# BIT_Level_Shift.net
KiCad netlist of a schematic drawn in Altium Designer
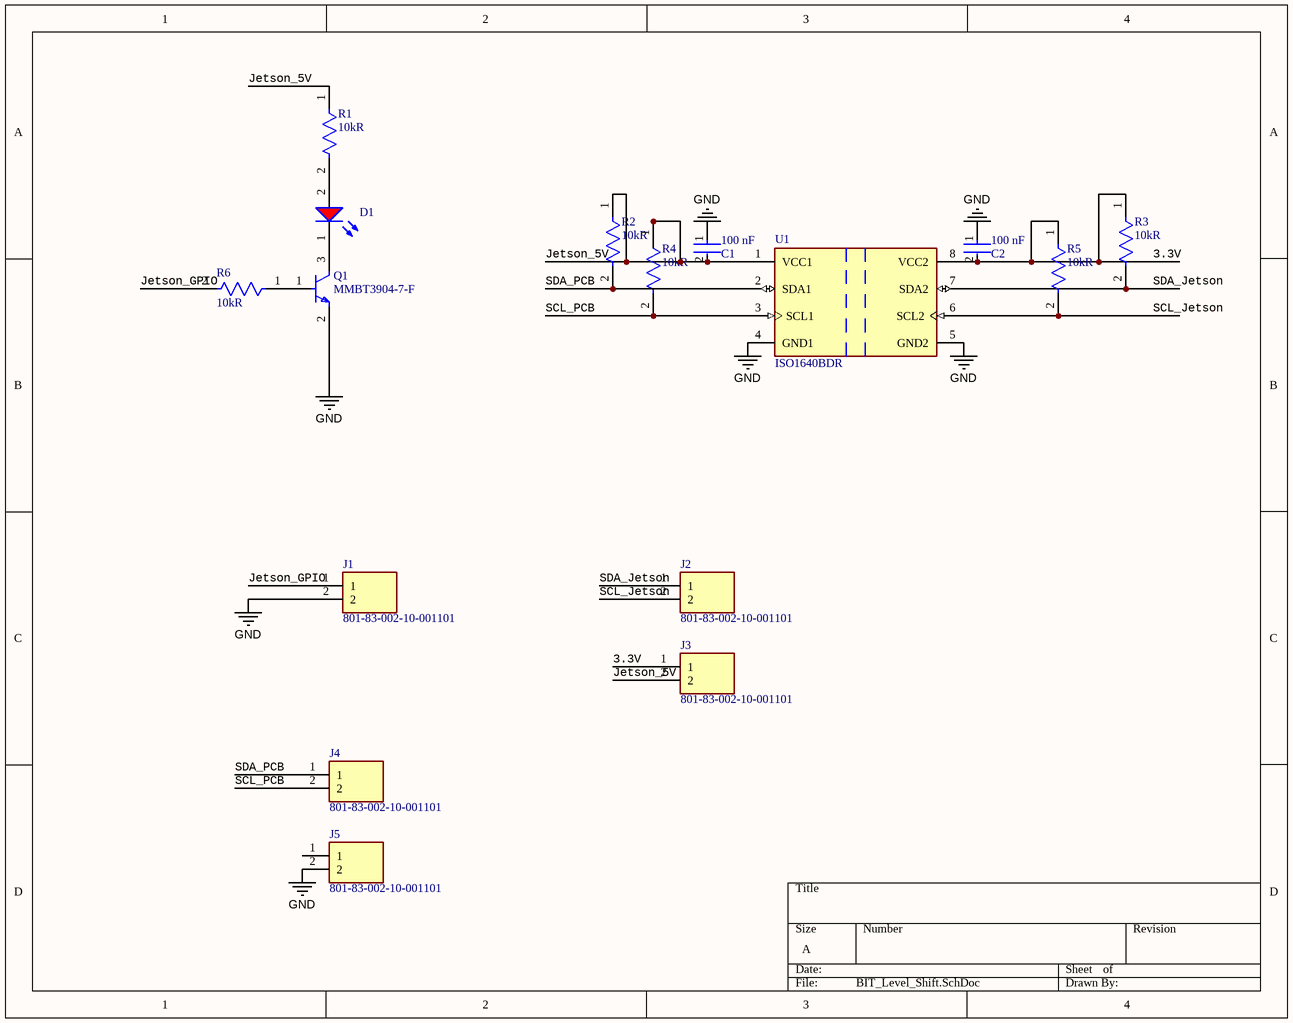
[diagram p0: BIT_Level_Shift.SchDoc]

(export (version "E")
  (design (tool "Eeschema 10.0.6"))
  (components
    (comp (ref "C1")
      (value "CC0805KRX7R9BB104")
      (footprint "FP-CC0805-0_85-MFG")
      (description "CAP CER 0.1UF 50V X7R 0805")
      (fields
        (field (name "TOLERANCE") "0.1")
        (field (name "CAPACITANCE") "100 nF")
        (field (name "MANUFACTURER") "Yageo")
      )
      (libsource (lib "Altium Content Vault") (part "11868f565c42a9108669ba33697ecf6"))
    )
    (comp (ref "C2")
      (value "CC0805KRX7R9BB104")
      (footprint "FP-CC0805-0_85-MFG")
      (description "CAP CER 0.1UF 50V X7R 0805")
      (fields
        (field (name "TOLERANCE") "0.1")
        (field (name "CAPACITANCE") "100 nF")
        (field (name "MANUFACTURER") "Yageo")
      )
      (libsource (lib "Altium Content Vault") (part "11868f565c42a9108669ba33697ecf6"))
    )
    (comp (ref "D1")
      (value "150080RS75000")
      (footprint "WL-SMCW_0805_150080xx75000")
      (description "LED Uni-Color Red 630nm 2-Pin Chip 0805(2012Metric) T/R")
      (libsource (lib "Altium Content Vault") (part "LED_Red_2A-1K"))
    )
    (comp (ref "J1")
      (value "801-83-002-10-001101")
      (footprint "SamacSys:RHDR2W60P0X254_1X2_508X254X700P")
      (description "Connector")
      (fields (field (name "MOUSER PART NUMBER") "437-8018300210001101"))
      (libsource (lib "*") (part "801-83-002-10-001101"))
    )
    (comp (ref "J2")
      (value "801-83-002-10-001101")
      (footprint "SamacSys:RHDR2W60P0X254_1X2_508X254X700P")
      (description "Connector")
      (fields (field (name "MOUSER PART NUMBER") "437-8018300210001101"))
      (libsource (lib "*") (part "801-83-002-10-001101"))
    )
    (comp (ref "J3")
      (value "801-83-002-10-001101")
      (footprint "SamacSys:RHDR2W60P0X254_1X2_508X254X700P")
      (description "Connector")
      (fields (field (name "MOUSER PART NUMBER") "437-8018300210001101"))
      (libsource (lib "*") (part "801-83-002-10-001101"))
    )
    (comp (ref "J4")
      (value "801-83-002-10-001101")
      (footprint "SamacSys:RHDR2W60P0X254_1X2_508X254X700P")
      (description "Connector")
      (fields (field (name "MOUSER PART NUMBER") "437-8018300210001101"))
      (libsource (lib "*") (part "801-83-002-10-001101"))
    )
    (comp (ref "J5")
      (value "801-83-002-10-001101")
      (footprint "SamacSys:RHDR2W60P0X254_1X2_508X254X700P")
      (description "Connector")
      (fields (field (name "MOUSER PART NUMBER") "437-8018300210001101"))
      (libsource (lib "*") (part "801-83-002-10-001101"))
    )
    (comp (ref "Q1")
      (value "MMBT3904-7-F")
      (footprint "FP-SOT23-IPC_A")
      (description "TRANS NPN 40V 0.2A SMD SOT23-3")
      (libsource (lib "Altium Content Vault") (part "b44e953556f554d0102664c7d152cb4"))
    )
    (comp (ref "R1")
      (value "RR1220P-103-D")
      (footprint "FP-RR1220-IPC_A")
      (description "10kΩ ±0.5% 0.1W 1/10W Chip Resistor 0805 (2012 Metric) Thin Film")
      (fields (field (name "RESISTANCE") "10kR") (field (name "TOLERANCE") "0.5%"))
      (libsource (lib "Altium Content Vault") (part "1029c3af85768c4190bb7ad29bc67b5"))
    )
    (comp (ref "R2")
      (value "RR1220P-103-D")
      (footprint "FP-RR1220-IPC_A")
      (description "10kΩ ±0.5% 0.1W 1/10W Chip Resistor 0805 (2012 Metric) Thin Film")
      (fields (field (name "RESISTANCE") "10kR") (field (name "TOLERANCE") "0.5%"))
      (libsource (lib "Altium Content Vault") (part "1029c3af85768c4190bb7ad29bc67b5"))
    )
    (comp (ref "R3")
      (value "RR1220P-103-D")
      (footprint "FP-RR1220-IPC_A")
      (description "10kΩ ±0.5% 0.1W 1/10W Chip Resistor 0805 (2012 Metric) Thin Film")
      (fields (field (name "RESISTANCE") "10kR") (field (name "TOLERANCE") "0.5%"))
      (libsource (lib "Altium Content Vault") (part "1029c3af85768c4190bb7ad29bc67b5"))
    )
    (comp (ref "R4")
      (value "RR1220P-103-D")
      (footprint "FP-RR1220-IPC_A")
      (description "10kΩ ±0.5% 0.1W 1/10W Chip Resistor 0805 (2012 Metric) Thin Film")
      (fields (field (name "RESISTANCE") "10kR") (field (name "TOLERANCE") "0.5%"))
      (libsource (lib "Altium Content Vault") (part "1029c3af85768c4190bb7ad29bc67b5"))
    )
    (comp (ref "R5")
      (value "RR1220P-103-D")
      (footprint "FP-RR1220-IPC_A")
      (description "10kΩ ±0.5% 0.1W 1/10W Chip Resistor 0805 (2012 Metric) Thin Film")
      (fields (field (name "RESISTANCE") "10kR") (field (name "TOLERANCE") "0.5%"))
      (libsource (lib "Altium Content Vault") (part "1029c3af85768c4190bb7ad29bc67b5"))
    )
    (comp (ref "R6")
      (value "RR1220P-103-D")
      (footprint "FP-RR1220-IPC_A")
      (description "10kΩ ±0.5% 0.1W 1/10W Chip Resistor 0805 (2012 Metric) Thin Film")
      (fields (field (name "RESISTANCE") "10kR") (field (name "TOLERANCE") "0.5%"))
      (libsource (lib "Altium Content Vault") (part "1029c3af85768c4190bb7ad29bc67b5"))
    )
    (comp (ref "U1")
      (value "ISO1640BDR")
      (footprint "FP-D0008A-IPC_C")
      (description "ROBUST-EMC BIDIRECTIONAL I2C DIG")
      (libsource (lib "Altium Content Vault") (part "4cc1386e94c7f9b5035976a599e6ca5"))
    )
  )
  (nets
    (net (code "1") (name "/3.3V") (class "Default")
      (node (ref "C2") (pin "2") (pinfunction "2_2") (pintype "passive"))
      (node (ref "J3") (pin "1") (pinfunction "1_1") (pintype "passive"))
      (node (ref "R3") (pin "1") (pinfunction "1_1") (pintype "passive"))
      (node (ref "R5") (pin "1") (pinfunction "1_1") (pintype "passive"))
      (node (ref "U1") (pin "8") (pinfunction "VCC2_8") (pintype "power_in"))
    )
    (net (code "2") (name "/Jetson_5V") (class "Default")
      (node (ref "C1") (pin "2") (pinfunction "2_2") (pintype "passive"))
      (node (ref "J3") (pin "2") (pinfunction "2_2") (pintype "passive"))
      (node (ref "R1") (pin "1") (pinfunction "1_1") (pintype "passive"))
      (node (ref "R2") (pin "1") (pinfunction "1_1") (pintype "passive"))
      (node (ref "R4") (pin "1") (pinfunction "1_1") (pintype "passive"))
      (node (ref "U1") (pin "1") (pinfunction "VCC1_1") (pintype "power_in"))
    )
    (net (code "3") (name "/Jetson_GPIO") (class "Default")
      (node (ref "J1") (pin "1") (pinfunction "1_1") (pintype "passive"))
      (node (ref "R6") (pin "2") (pinfunction "2_2") (pintype "passive"))
    )
    (net (code "4") (name "/SCL_Jetson") (class "Default")
      (node (ref "J2") (pin "2") (pinfunction "2_2") (pintype "passive"))
      (node (ref "R5") (pin "2") (pinfunction "2_2") (pintype "passive"))
      (node (ref "U1") (pin "6") (pinfunction "SCL2_6") (pintype "input"))
    )
    (net (code "5") (name "/SCL_PCB") (class "Default")
      (node (ref "J4") (pin "2") (pinfunction "2_2") (pintype "passive"))
      (node (ref "R4") (pin "2") (pinfunction "2_2") (pintype "passive"))
      (node (ref "U1") (pin "3") (pinfunction "SCL1_3") (pintype "input"))
    )
    (net (code "6") (name "/SDA_Jetson") (class "Default")
      (node (ref "J2") (pin "1") (pinfunction "1_1") (pintype "passive"))
      (node (ref "R3") (pin "2") (pinfunction "2_2") (pintype "passive"))
      (node (ref "U1") (pin "7") (pinfunction "SDA2_7") (pintype "bidirectional"))
    )
    (net (code "7") (name "/SDA_PCB") (class "Default")
      (node (ref "J4") (pin "1") (pinfunction "1_1") (pintype "passive"))
      (node (ref "R2") (pin "2") (pinfunction "2_2") (pintype "passive"))
      (node (ref "U1") (pin "2") (pinfunction "SDA1_2") (pintype "bidirectional"))
    )
    (net (code "8") (name "GND") (class "Default")
      (node (ref "C1") (pin "1") (pinfunction "1_1") (pintype "passive"))
      (node (ref "C2") (pin "1") (pinfunction "1_1") (pintype "passive"))
      (node (ref "J1") (pin "2") (pinfunction "2_2") (pintype "passive"))
      (node (ref "J5") (pin "2") (pinfunction "2_2") (pintype "passive"))
      (node (ref "Q1") (pin "2") (pinfunction "E_2") (pintype "passive"))
      (node (ref "U1") (pin "4") (pinfunction "GND1_4") (pintype "power_in"))
      (node (ref "U1") (pin "5") (pinfunction "GND2_5") (pintype "power_in"))
    )
    (net (code "9") (name "Net-(D1-A)") (class "Default")
      (node (ref "D1") (pin "2") (pinfunction "A_2") (pintype "passive"))
      (node (ref "R1") (pin "2") (pinfunction "2_2") (pintype "passive"))
    )
    (net (code "10") (name "Net-(D1-K)") (class "Default")
      (node (ref "D1") (pin "1") (pinfunction "K_1") (pintype "passive"))
      (node (ref "Q1") (pin "3") (pinfunction "C_3") (pintype "passive"))
    )
    (net (code "11") (name "Net-(Q1-B)") (class "Default")
      (node (ref "Q1") (pin "1") (pinfunction "B_1") (pintype "passive"))
      (node (ref "R6") (pin "1") (pinfunction "1_1") (pintype "passive"))
    )
    (net (code "12") (name "unconnected-(J5-Pad1)") (class "Default")
      (node (ref "J5") (pin "1") (pinfunction "1_1") (pintype "passive"))
    )
  )
)
